# eggfckr.net
KiCad netlist of a schematic drawn in EAGLE
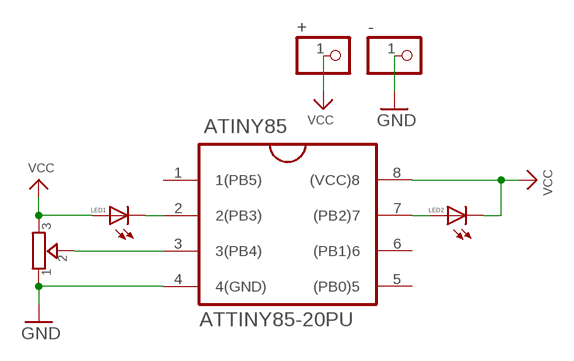
[diagram p0: schematic, sheet 1]

(export (version "E")
  (design (tool "Eeschema 10.0.6"))
  (components
    (comp (ref "+")
      (value "HEADER-1X1")
      (footprint "eagle-import:1X01_OVAL")
      (libsource (lib "eagle-import") (part "HEADER-1X1"))
    )
    (comp (ref "-")
      (value "HEADER-1X1")
      (footprint "eagle-import:1X01_OVAL")
      (libsource (lib "eagle-import") (part "HEADER-1X1"))
    )
    (comp (ref "ATINY85")
      (value "ATTINY85-20PU")
      (footprint "eagle-import:DIP254P762X533-8")
      (libsource (lib "eagle-import") (part "ATTINY85-20PU"))
    )
    (comp (ref "LED1")
      (value "LED3MM")
      (footprint "eagle-import:LED3MM")
      (libsource (lib "eagle-import") (part "LED3MM"))
    )
    (comp (ref "LED2")
      (value "LED3MM")
      (footprint "eagle-import:LED3MM")
      (libsource (lib "eagle-import") (part "LED3MM"))
    )
    (comp (ref "R3")
      (value "TRIMMER-3306F")
      (footprint "eagle-import:TRIMMER_3306F")
      (libsource (lib "eagle-import") (part "TRIMMER-3306F"))
    )
  )
  (nets
    (net (code "1") (name "GND") (class "Default")
      (node (ref "-") (pin "1") (pinfunction "1_1") (pintype "passive"))
      (node (ref "ATINY85") (pin "4") (pinfunction "4(GND)_4") (pintype "passive"))
      (node (ref "R3") (pin "1") (pinfunction "1_1") (pintype "passive"))
    )
    (net (code "2") (name "Net-(ATINY85-(PB2)7)") (class "Default")
      (node (ref "ATINY85") (pin "7") (pinfunction "(PB2)7_7") (pintype "bidirectional"))
      (node (ref "LED2") (pin "A") (pinfunction "A_A") (pintype "passive"))
    )
    (net (code "3") (name "Net-(ATINY85-2(PB3))") (class "Default")
      (node (ref "ATINY85") (pin "2") (pinfunction "2(PB3)_2") (pintype "bidirectional"))
      (node (ref "LED1") (pin "K") (pinfunction "C_K") (pintype "passive"))
    )
    (net (code "4") (name "Net-(ATINY85-3(PB4))") (class "Default")
      (node (ref "ATINY85") (pin "3") (pinfunction "3(PB4)_3") (pintype "bidirectional"))
      (node (ref "R3") (pin "2") (pinfunction "2_2") (pintype "passive"))
    )
    (net (code "5") (name "VCC") (class "Default")
      (node (ref "+") (pin "1") (pinfunction "1_1") (pintype "passive"))
      (node (ref "ATINY85") (pin "8") (pinfunction "(VCC)8_8") (pintype "power_in"))
      (node (ref "LED1") (pin "A") (pinfunction "A_A") (pintype "passive"))
      (node (ref "LED2") (pin "K") (pinfunction "C_K") (pintype "passive"))
      (node (ref "R3") (pin "3") (pinfunction "3_3") (pintype "passive"))
    )
    (net (code "6") (name "unconnected-(ATINY85-(PB0)5-Pad5)") (class "Default")
      (node (ref "ATINY85") (pin "5") (pinfunction "(PB0)5_5") (pintype "bidirectional"))
    )
    (net (code "7") (name "unconnected-(ATINY85-(PB1)6-Pad6)") (class "Default")
      (node (ref "ATINY85") (pin "6") (pinfunction "(PB1)6_6") (pintype "bidirectional"))
    )
    (net (code "8") (name "unconnected-(ATINY85-1(PB5)-Pad1)") (class "Default")
      (node (ref "ATINY85") (pin "1") (pinfunction "1(PB5)_1") (pintype "bidirectional"))
    )
  )
)
